# Papilio-VGA_Wing.net
KiCad netlist of a schematic drawn in EAGLE
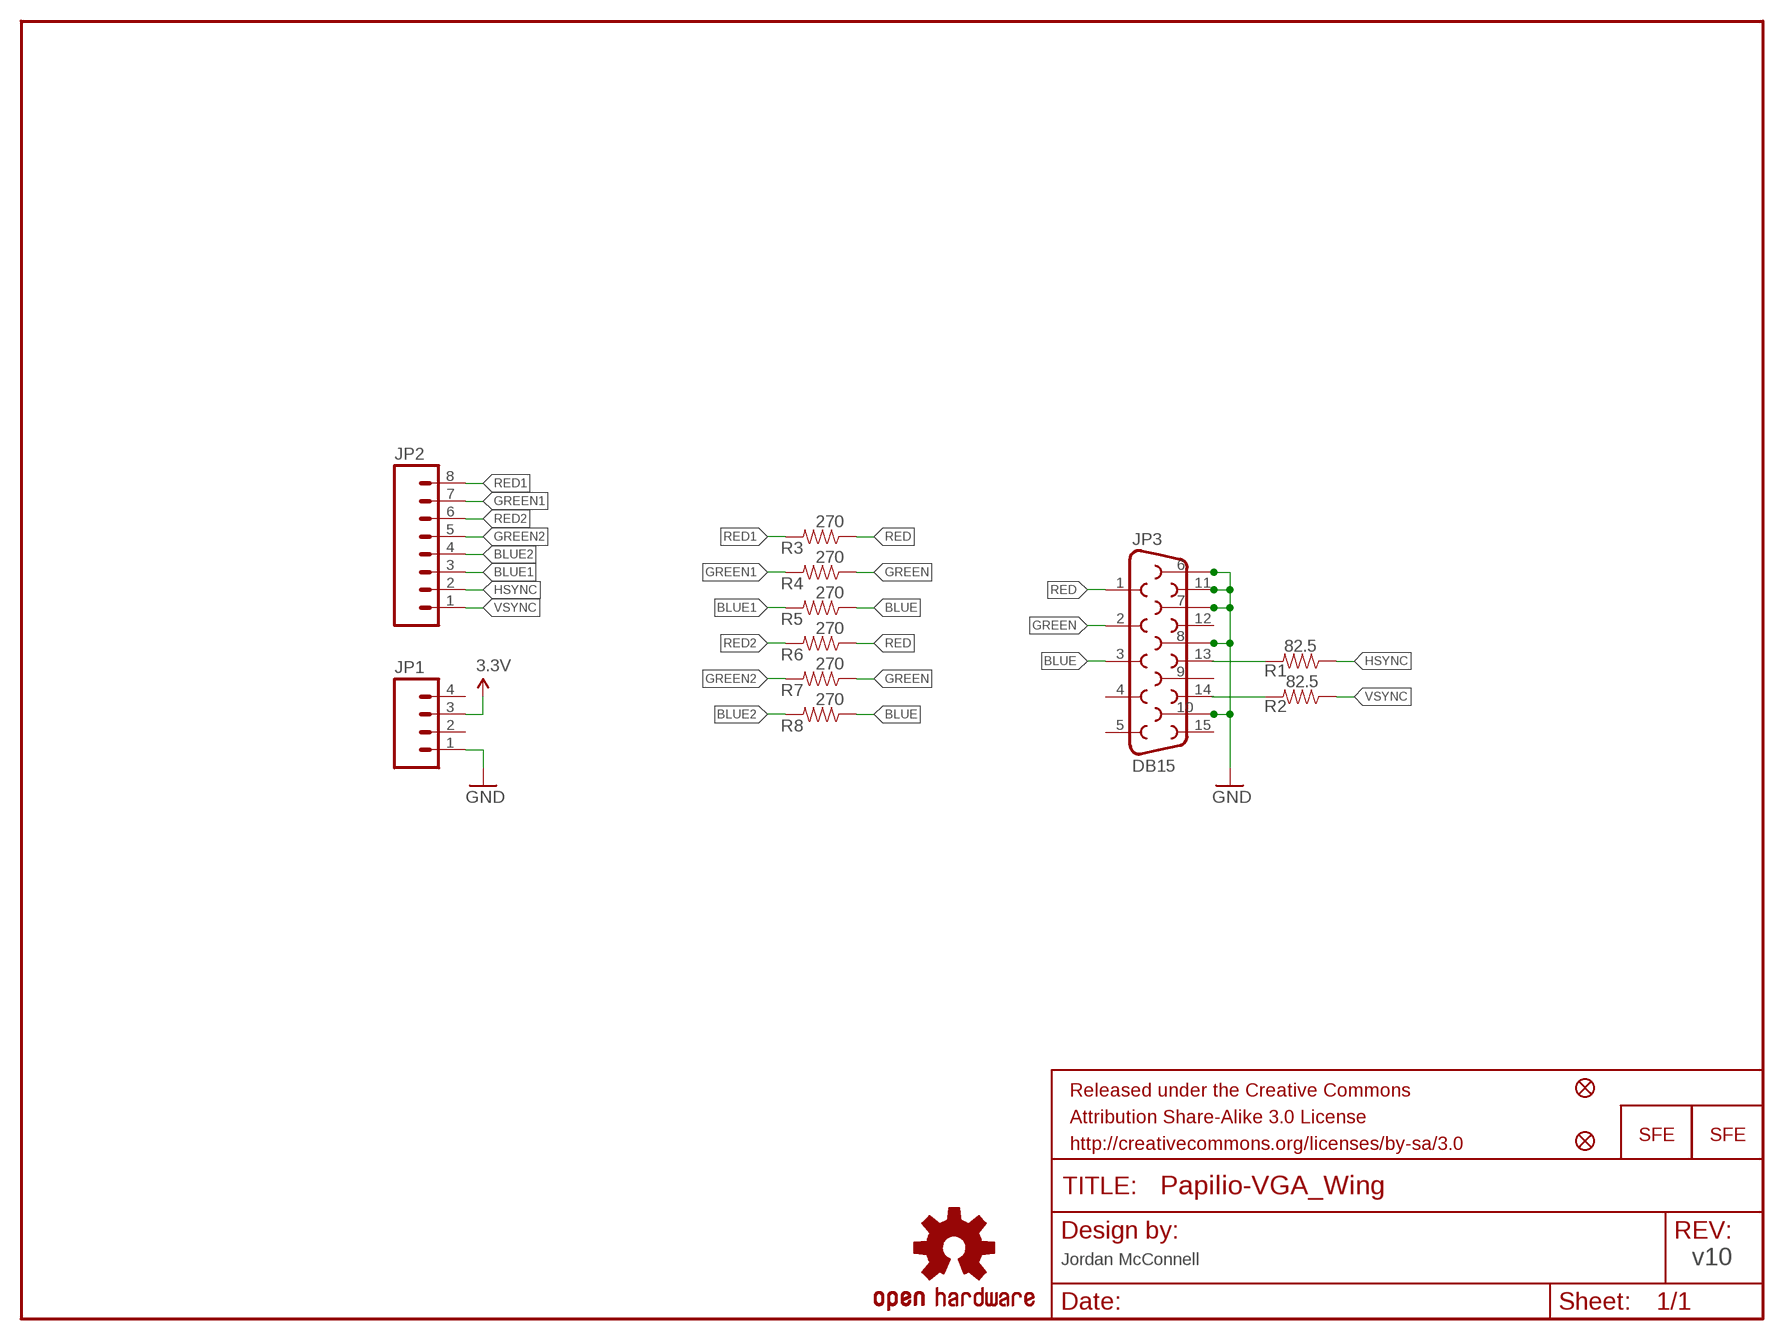
[diagram p0: schematic, sheet 1]

(export (version "E")
  (design (tool "Eeschema 10.0.6"))
  (components
    (comp (ref "FRAME1")
      (value "FRAME-LETTER")
      (footprint "eagle-import:CREATIVE_COMMONS")
      (libsource (lib "eagle-import") (part "FRAME-LETTER"))
    )
    (comp (ref "JP1")
      (value "M04PTH")
      (footprint "eagle-import:1X04")
      (libsource (lib "eagle-import") (part "M04PTH"))
    )
    (comp (ref "JP2")
      (value "M081X08")
      (footprint "eagle-import:1X08")
      (libsource (lib "eagle-import") (part "M081X08"))
    )
    (comp (ref "JP3")
      (value "DB15")
      (footprint "eagle-import:DB15")
      (libsource (lib "eagle-import") (part "DB15"))
    )
    (comp (ref "JP4")
      (value "FIDUCIALUFIDUCIAL")
      (footprint "eagle-import:MICRO-FIDUCIAL")
      (libsource (lib "eagle-import") (part "FIDUCIALUFIDUCIAL"))
    )
    (comp (ref "JP5")
      (value "FIDUCIALUFIDUCIAL")
      (footprint "eagle-import:MICRO-FIDUCIAL")
      (libsource (lib "eagle-import") (part "FIDUCIALUFIDUCIAL"))
    )
    (comp (ref "JP6")
      (value "LOGO-SFENEW")
      (footprint "eagle-import:SFE-NEW-WEBLOGO")
      (libsource (lib "eagle-import") (part "LOGO-SFENEW"))
    )
    (comp (ref "JP7")
      (value "LOGO-SFESK")
      (footprint "eagle-import:SFE-LOGO-FLAME")
      (libsource (lib "eagle-import") (part "LOGO-SFESK"))
    )
    (comp (ref "R1")
      (value "82.5")
      (footprint "eagle-import:0402-RES")
      (libsource (lib "eagle-import") (part "RESISTOR0402-RES"))
    )
    (comp (ref "R2")
      (value "82.5")
      (footprint "eagle-import:0402-RES")
      (libsource (lib "eagle-import") (part "RESISTOR0402-RES"))
    )
    (comp (ref "R3")
      (value "270")
      (footprint "eagle-import:0402-RES")
      (libsource (lib "eagle-import") (part "RESISTOR0402-RES"))
    )
    (comp (ref "R4")
      (value "270")
      (footprint "eagle-import:0402-RES")
      (libsource (lib "eagle-import") (part "RESISTOR0402-RES"))
    )
    (comp (ref "R5")
      (value "270")
      (footprint "eagle-import:0402-RES")
      (libsource (lib "eagle-import") (part "RESISTOR0402-RES"))
    )
    (comp (ref "R6")
      (value "270")
      (footprint "eagle-import:0402-RES")
      (libsource (lib "eagle-import") (part "RESISTOR0402-RES"))
    )
    (comp (ref "R7")
      (value "270")
      (footprint "eagle-import:0402-RES")
      (libsource (lib "eagle-import") (part "RESISTOR0402-RES"))
    )
    (comp (ref "R8")
      (value "270")
      (footprint "eagle-import:0402-RES")
      (libsource (lib "eagle-import") (part "RESISTOR0402-RES"))
    )
    (comp (ref "U$1")
      (value "OSHW-LOGOS")
      (footprint "eagle-import:OSHW-LOGO-S")
      (libsource (lib "eagle-import") (part "OSHW-LOGOS"))
    )
  )
  (nets
    (net (code "1") (name "3.3V") (class "Default")
      (node (ref "JP1") (pin "3") (pinfunction "3_3") (pintype "passive"))
    )
    (net (code "2") (name "BLUE") (class "Default")
      (node (ref "JP3") (pin "3") (pinfunction "3_3") (pintype "passive"))
      (node (ref "R5") (pin "1") (pinfunction "1_1") (pintype "passive"))
      (node (ref "R8") (pin "1") (pinfunction "1_1") (pintype "passive"))
    )
    (net (code "3") (name "BLUE1") (class "Default")
      (node (ref "JP2") (pin "3") (pinfunction "3_3") (pintype "passive"))
      (node (ref "R5") (pin "2") (pinfunction "2_2") (pintype "passive"))
    )
    (net (code "4") (name "BLUE2") (class "Default")
      (node (ref "JP2") (pin "4") (pinfunction "4_4") (pintype "passive"))
      (node (ref "R8") (pin "2") (pinfunction "2_2") (pintype "passive"))
    )
    (net (code "5") (name "GND") (class "Default")
      (node (ref "JP1") (pin "1") (pinfunction "1_1") (pintype "passive"))
      (node (ref "JP3") (pin "10") (pinfunction "10_10") (pintype "passive"))
      (node (ref "JP3") (pin "11") (pinfunction "11_11") (pintype "passive"))
      (node (ref "JP3") (pin "6") (pinfunction "6_6") (pintype "passive"))
      (node (ref "JP3") (pin "7") (pinfunction "7_7") (pintype "passive"))
      (node (ref "JP3") (pin "8") (pinfunction "8_8") (pintype "passive"))
    )
    (net (code "6") (name "GREEN") (class "Default")
      (node (ref "JP3") (pin "2") (pinfunction "2_2") (pintype "passive"))
      (node (ref "R4") (pin "1") (pinfunction "1_1") (pintype "passive"))
      (node (ref "R7") (pin "1") (pinfunction "1_1") (pintype "passive"))
    )
    (net (code "7") (name "GREEN1") (class "Default")
      (node (ref "JP2") (pin "7") (pinfunction "7_7") (pintype "passive"))
      (node (ref "R4") (pin "2") (pinfunction "2_2") (pintype "passive"))
    )
    (net (code "8") (name "GREEN2") (class "Default")
      (node (ref "JP2") (pin "5") (pinfunction "5_5") (pintype "passive"))
      (node (ref "R7") (pin "2") (pinfunction "2_2") (pintype "passive"))
    )
    (net (code "9") (name "HSYNC") (class "Default")
      (node (ref "JP2") (pin "2") (pinfunction "2_2") (pintype "passive"))
      (node (ref "R1") (pin "1") (pinfunction "1_1") (pintype "passive"))
    )
    (net (code "10") (name "Net-(JP3-Pad13)") (class "Default")
      (node (ref "JP3") (pin "13") (pinfunction "13_13") (pintype "passive"))
      (node (ref "R1") (pin "2") (pinfunction "2_2") (pintype "passive"))
    )
    (net (code "11") (name "Net-(JP3-Pad14)") (class "Default")
      (node (ref "JP3") (pin "14") (pinfunction "14_14") (pintype "passive"))
      (node (ref "R2") (pin "2") (pinfunction "2_2") (pintype "passive"))
    )
    (net (code "12") (name "RED") (class "Default")
      (node (ref "JP3") (pin "1") (pinfunction "1_1") (pintype "passive"))
      (node (ref "R3") (pin "1") (pinfunction "1_1") (pintype "passive"))
      (node (ref "R6") (pin "1") (pinfunction "1_1") (pintype "passive"))
    )
    (net (code "13") (name "RED1") (class "Default")
      (node (ref "JP2") (pin "8") (pinfunction "8_8") (pintype "passive"))
      (node (ref "R3") (pin "2") (pinfunction "2_2") (pintype "passive"))
    )
    (net (code "14") (name "RED2") (class "Default")
      (node (ref "JP2") (pin "6") (pinfunction "6_6") (pintype "passive"))
      (node (ref "R6") (pin "2") (pinfunction "2_2") (pintype "passive"))
    )
    (net (code "15") (name "VSYNC") (class "Default")
      (node (ref "JP2") (pin "1") (pinfunction "1_1") (pintype "passive"))
      (node (ref "R2") (pin "1") (pinfunction "1_1") (pintype "passive"))
    )
    (net (code "16") (name "unconnected-(JP1-Pad2)") (class "Default")
      (node (ref "JP1") (pin "2") (pinfunction "2_2") (pintype "passive"))
    )
    (net (code "17") (name "unconnected-(JP1-Pad4)") (class "Default")
      (node (ref "JP1") (pin "4") (pinfunction "4_4") (pintype "passive"))
    )
    (net (code "18") (name "unconnected-(JP3-Pad4)") (class "Default")
      (node (ref "JP3") (pin "4") (pinfunction "4_4") (pintype "passive"))
    )
    (net (code "19") (name "unconnected-(JP3-Pad5)") (class "Default")
      (node (ref "JP3") (pin "5") (pinfunction "5_5") (pintype "passive"))
    )
    (net (code "20") (name "unconnected-(JP3-Pad9)") (class "Default")
      (node (ref "JP3") (pin "9") (pinfunction "9_9") (pintype "passive"))
    )
    (net (code "21") (name "unconnected-(JP3-Pad12)") (class "Default")
      (node (ref "JP3") (pin "12") (pinfunction "12_12") (pintype "passive"))
    )
    (net (code "22") (name "unconnected-(JP3-Pad15)") (class "Default")
      (node (ref "JP3") (pin "15") (pinfunction "15_15") (pintype "passive"))
    )
  )
)
